# slothbot_sensor_unit_3_0.net
KiCad netlist of a schematic drawn in EAGLE
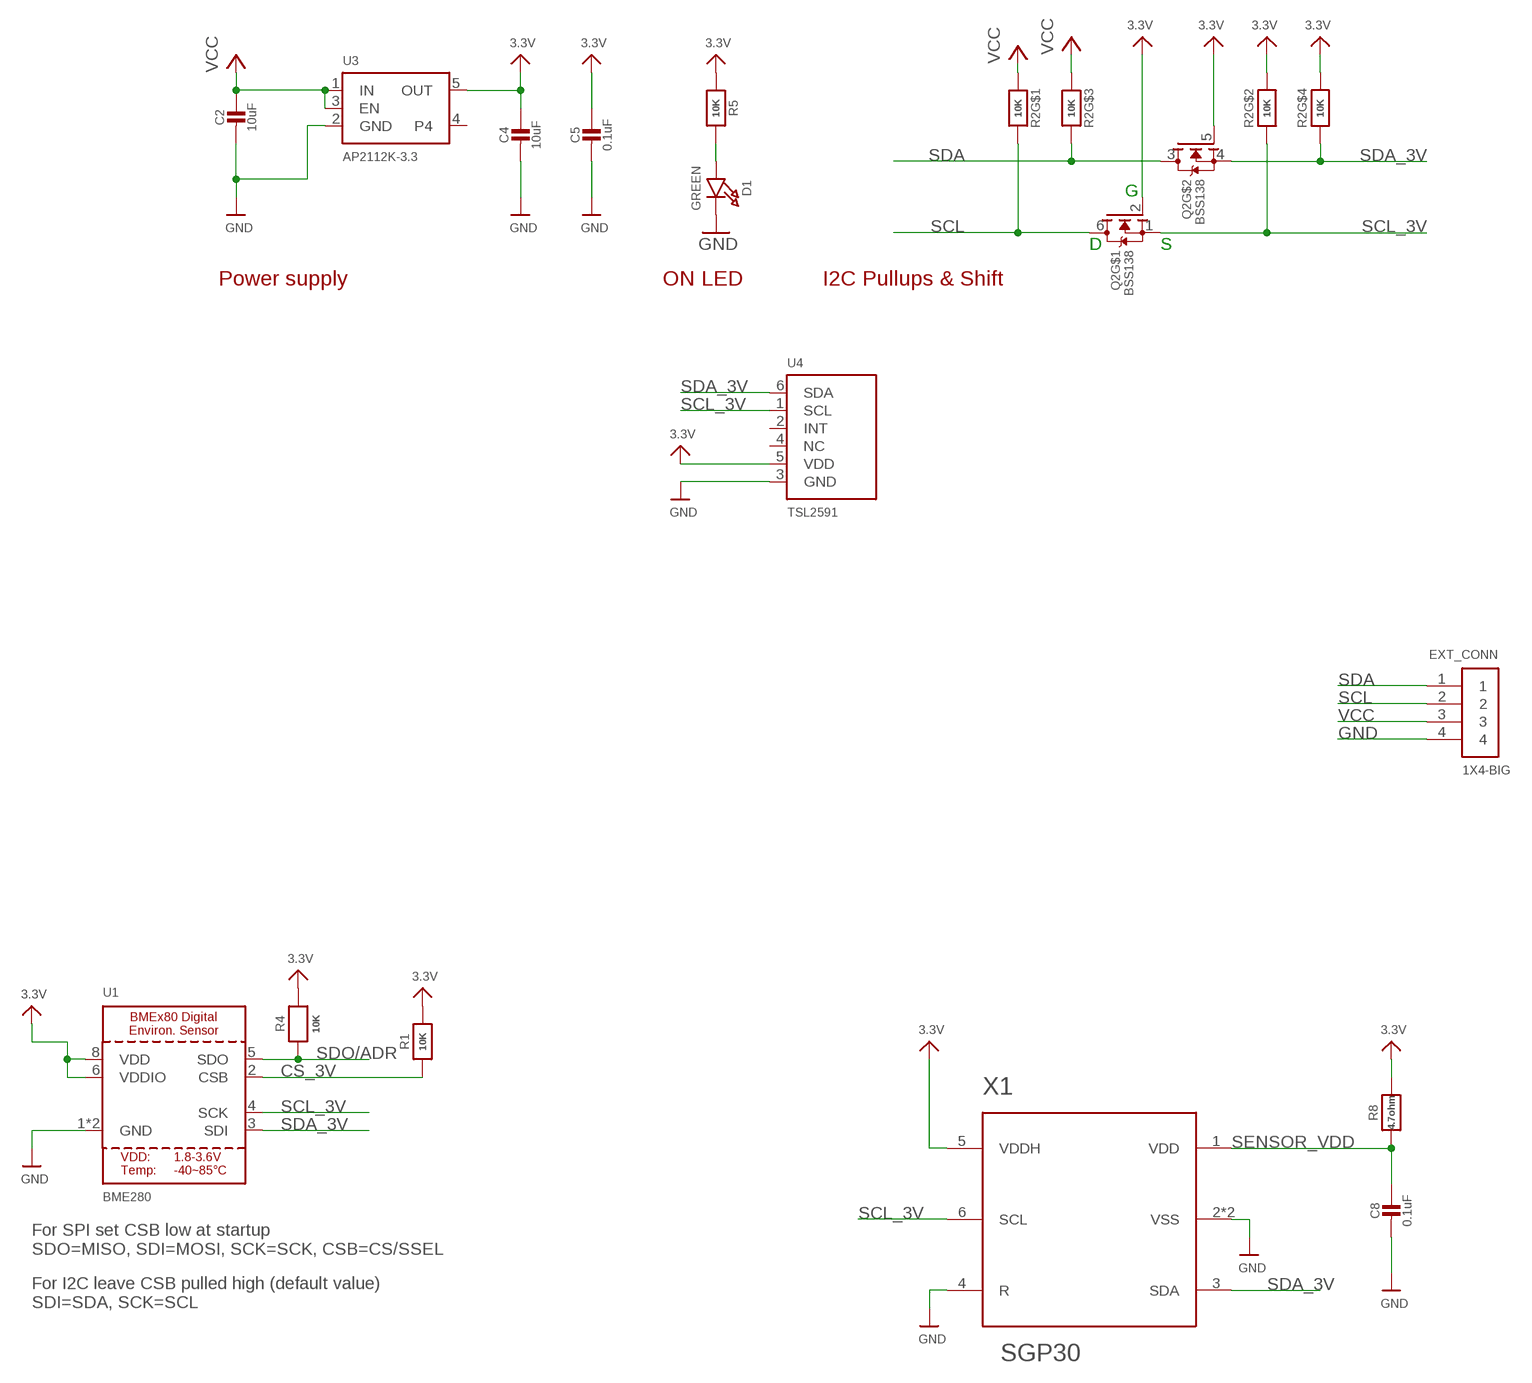
[diagram p0: schematic, sheet 1]

(export (version "E")
  (design (tool "Eeschema 10.0.6"))
  (components
    (comp (ref "C2")
      (value "10uF")
      (footprint "eagle-import:0805-NO")
      (libsource (lib "eagle-import") (part "CAP_CERAMIC0805-NOOUTLINE"))
    )
    (comp (ref "C4")
      (value "10uF")
      (footprint "eagle-import:0805-NO")
      (libsource (lib "eagle-import") (part "CAP_CERAMIC0805-NOOUTLINE"))
    )
    (comp (ref "C5")
      (value "0.1uF")
      (footprint "eagle-import:0603-NO")
      (libsource (lib "eagle-import") (part "CAP_CERAMIC0603_NO"))
    )
    (comp (ref "C8")
      (value "0.1uF")
      (footprint "eagle-import:0603-NO")
      (libsource (lib "eagle-import") (part "CAP_CERAMIC0603_NO"))
    )
    (comp (ref "D1")
      (value "GREEN")
      (footprint "eagle-import:CHIPLED_0603_NOOUTLINE")
      (libsource (lib "eagle-import") (part "LED0603_NOOUTLINE"))
    )
    (comp (ref "EXT_CONN")
      (value "1X4-BIG")
      (footprint "eagle-import:1X04-BIG")
      (libsource (lib "eagle-import") (part "1X4-BIG"))
    )
    (comp (ref "Q2")
      (value "BSS138")
      (footprint "eagle-import:SOT363")
      (libsource (lib "eagle-import") (part "MOSFET-N_DUAL"))
    )
    (comp (ref "R1")
      (value "10K")
      (footprint "eagle-import:0603-NO")
      (libsource (lib "eagle-import") (part "RESISTOR_0603_NOOUT"))
    )
    (comp (ref "R2")
      (value "10K")
      (footprint "eagle-import:RESPACK_4X0603")
      (libsource (lib "eagle-import") (part "RESISTOR_4PACK"))
    )
    (comp (ref "R4")
      (value "10K")
      (footprint "eagle-import:0603-NO")
      (libsource (lib "eagle-import") (part "RESISTOR_0603_NOOUT"))
    )
    (comp (ref "R5")
      (value "10K")
      (footprint "eagle-import:0603-NO")
      (libsource (lib "eagle-import") (part "RESISTOR_0603_NOOUT"))
    )
    (comp (ref "R8")
      (value "4.7ohm")
      (footprint "eagle-import:0603-NO")
      (libsource (lib "eagle-import") (part "RESISTOR_0603_NOOUT"))
    )
    (comp (ref "U1")
      (value "BME280")
      (footprint "eagle-import:BME280")
      (libsource (lib "eagle-import") (part "BME280"))
    )
    (comp (ref "U3")
      (value "AP2112K-3.3")
      (footprint "eagle-import:SOT23-5")
      (libsource (lib "eagle-import") (part "VREG_SOT23-5"))
    )
    (comp (ref "U4")
      (value "TSL2591")
      (footprint "eagle-import:DFN6_TAOS")
      (libsource (lib "eagle-import") (part "LIGHT_TSL2591"))
    )
    (comp (ref "X1")
      (value "SGP30")
      (footprint "eagle-import:SGP30")
      (libsource (lib "eagle-import") (part "SGP30"))
    )
  )
  (nets
    (net (code "1") (name "/CS_3V") (class "Default")
      (node (ref "R1") (pin "1") (pinfunction "1_1") (pintype "passive"))
      (node (ref "U1") (pin "2") (pinfunction "CSB_2") (pintype "input"))
    )
    (net (code "2") (name "/SCL") (class "Default")
      (node (ref "EXT_CONN") (pin "2") (pinfunction "2_2") (pintype "bidirectional"))
      (node (ref "Q2") (pin "6") (pinfunction "D_6") (pintype "bidirectional"))
      (node (ref "R2") (pin "8") (pinfunction "2_8") (pintype "passive"))
    )
    (net (code "3") (name "/SCL_3V") (class "Default")
      (node (ref "Q2") (pin "1") (pinfunction "S_1") (pintype "bidirectional"))
      (node (ref "R2") (pin "7") (pinfunction "2_7") (pintype "passive"))
      (node (ref "U1") (pin "4") (pinfunction "SCK_4") (pintype "input"))
      (node (ref "U4") (pin "1") (pinfunction "SCL_1") (pintype "bidirectional"))
      (node (ref "X1") (pin "6") (pinfunction "SCL_6") (pintype "bidirectional"))
    )
    (net (code "4") (name "/SDA") (class "Default")
      (node (ref "EXT_CONN") (pin "1") (pinfunction "1_1") (pintype "bidirectional"))
      (node (ref "Q2") (pin "3") (pinfunction "D_3") (pintype "bidirectional"))
      (node (ref "R2") (pin "6") (pinfunction "2_6") (pintype "passive"))
    )
    (net (code "5") (name "/SDA_3V") (class "Default")
      (node (ref "Q2") (pin "4") (pinfunction "S_4") (pintype "bidirectional"))
      (node (ref "R2") (pin "5") (pinfunction "2_5") (pintype "passive"))
      (node (ref "U1") (pin "3") (pinfunction "SDI_3") (pintype "input"))
      (node (ref "U4") (pin "6") (pinfunction "SDA_6") (pintype "bidirectional"))
      (node (ref "X1") (pin "3") (pinfunction "SDA_3") (pintype "bidirectional"))
    )
    (net (code "6") (name "/SDO{slash}ADR") (class "Default")
      (node (ref "R4") (pin "1") (pinfunction "1_1") (pintype "passive"))
      (node (ref "U1") (pin "5") (pinfunction "SDO_5") (pintype "output"))
    )
    (net (code "7") (name "/SENSOR_VDD") (class "Default")
      (node (ref "C8") (pin "1") (pinfunction "1_1") (pintype "passive"))
      (node (ref "R8") (pin "1") (pinfunction "1_1") (pintype "passive"))
      (node (ref "X1") (pin "1") (pinfunction "VDD_1") (pintype "bidirectional"))
    )
    (net (code "8") (name "3.3V") (class "Default")
      (node (ref "C4") (pin "1") (pinfunction "1_1") (pintype "passive"))
      (node (ref "C5") (pin "1") (pinfunction "1_1") (pintype "passive"))
      (node (ref "Q2") (pin "2") (pinfunction "G_2") (pintype "bidirectional"))
      (node (ref "Q2") (pin "5") (pinfunction "G_5") (pintype "bidirectional"))
      (node (ref "R1") (pin "2") (pinfunction "2_2") (pintype "passive"))
      (node (ref "R2") (pin "2") (pinfunction "1_2") (pintype "passive"))
      (node (ref "R2") (pin "4") (pinfunction "1_4") (pintype "passive"))
      (node (ref "R4") (pin "2") (pinfunction "2_2") (pintype "passive"))
      (node (ref "R5") (pin "1") (pinfunction "1_1") (pintype "passive"))
      (node (ref "R8") (pin "2") (pinfunction "2_2") (pintype "passive"))
      (node (ref "U1") (pin "6") (pinfunction "VDDIO_6") (pintype "power_in"))
      (node (ref "U1") (pin "8") (pinfunction "VDD_8") (pintype "power_in"))
      (node (ref "U3") (pin "5") (pinfunction "OUT_5") (pintype "power_in"))
      (node (ref "U4") (pin "5") (pinfunction "VDD_5") (pintype "power_in"))
      (node (ref "X1") (pin "5") (pinfunction "VDDH_5") (pintype "bidirectional"))
    )
    (net (code "9") (name "GND") (class "Default")
      (node (ref "C2") (pin "2") (pinfunction "2_2") (pintype "passive"))
      (node (ref "C4") (pin "2") (pinfunction "2_2") (pintype "passive"))
      (node (ref "C5") (pin "2") (pinfunction "2_2") (pintype "passive"))
      (node (ref "C8") (pin "2") (pinfunction "2_2") (pintype "passive"))
      (node (ref "D1") (pin "C") (pinfunction "C_C") (pintype "passive"))
      (node (ref "EXT_CONN") (pin "4") (pinfunction "4_4") (pintype "bidirectional"))
      (node (ref "U1") (pin "1") (pinfunction "GND_1") (pintype "power_in"))
      (node (ref "U1") (pin "7") (pinfunction "GND_7") (pintype "power_in"))
      (node (ref "U3") (pin "2") (pinfunction "GND_2") (pintype "power_in"))
      (node (ref "U4") (pin "3") (pinfunction "GND_3") (pintype "power_in"))
      (node (ref "X1") (pin "2") (pinfunction "VSS_2") (pintype "bidirectional"))
      (node (ref "X1") (pin "4") (pinfunction "R_4") (pintype "bidirectional"))
      (node (ref "X1") (pin "P$7") (pinfunction "VSS_P$7") (pintype "bidirectional"))
    )
    (net (code "10") (name "Net-(D1-PadA)") (class "Default")
      (node (ref "D1") (pin "A") (pinfunction "A_A") (pintype "passive"))
      (node (ref "R5") (pin "2") (pinfunction "2_2") (pintype "passive"))
    )
    (net (code "11") (name "VCC") (class "Default")
      (node (ref "C2") (pin "1") (pinfunction "1_1") (pintype "passive"))
      (node (ref "EXT_CONN") (pin "3") (pinfunction "3_3") (pintype "bidirectional"))
      (node (ref "R2") (pin "1") (pinfunction "1_1") (pintype "passive"))
      (node (ref "R2") (pin "3") (pinfunction "1_3") (pintype "passive"))
      (node (ref "U3") (pin "1") (pinfunction "IN_1") (pintype "power_in"))
      (node (ref "U3") (pin "3") (pinfunction "EN_3") (pintype "input"))
    )
    (net (code "12") (name "unconnected-(U3-P4-Pad4)") (class "Default")
      (node (ref "U3") (pin "4") (pinfunction "P4_4") (pintype "bidirectional"))
    )
    (net (code "13") (name "unconnected-(U4-INT-Pad2)") (class "Default")
      (node (ref "U4") (pin "2") (pinfunction "INT_2") (pintype "output"))
    )
    (net (code "14") (name "unconnected-(U4-NC-Pad4)") (class "Default")
      (node (ref "U4") (pin "4") (pinfunction "NC_4") (pintype "no_connect"))
    )
  )
)
